# easda-schema.net
KiCad netlist of a schematic drawn in EasyEDA
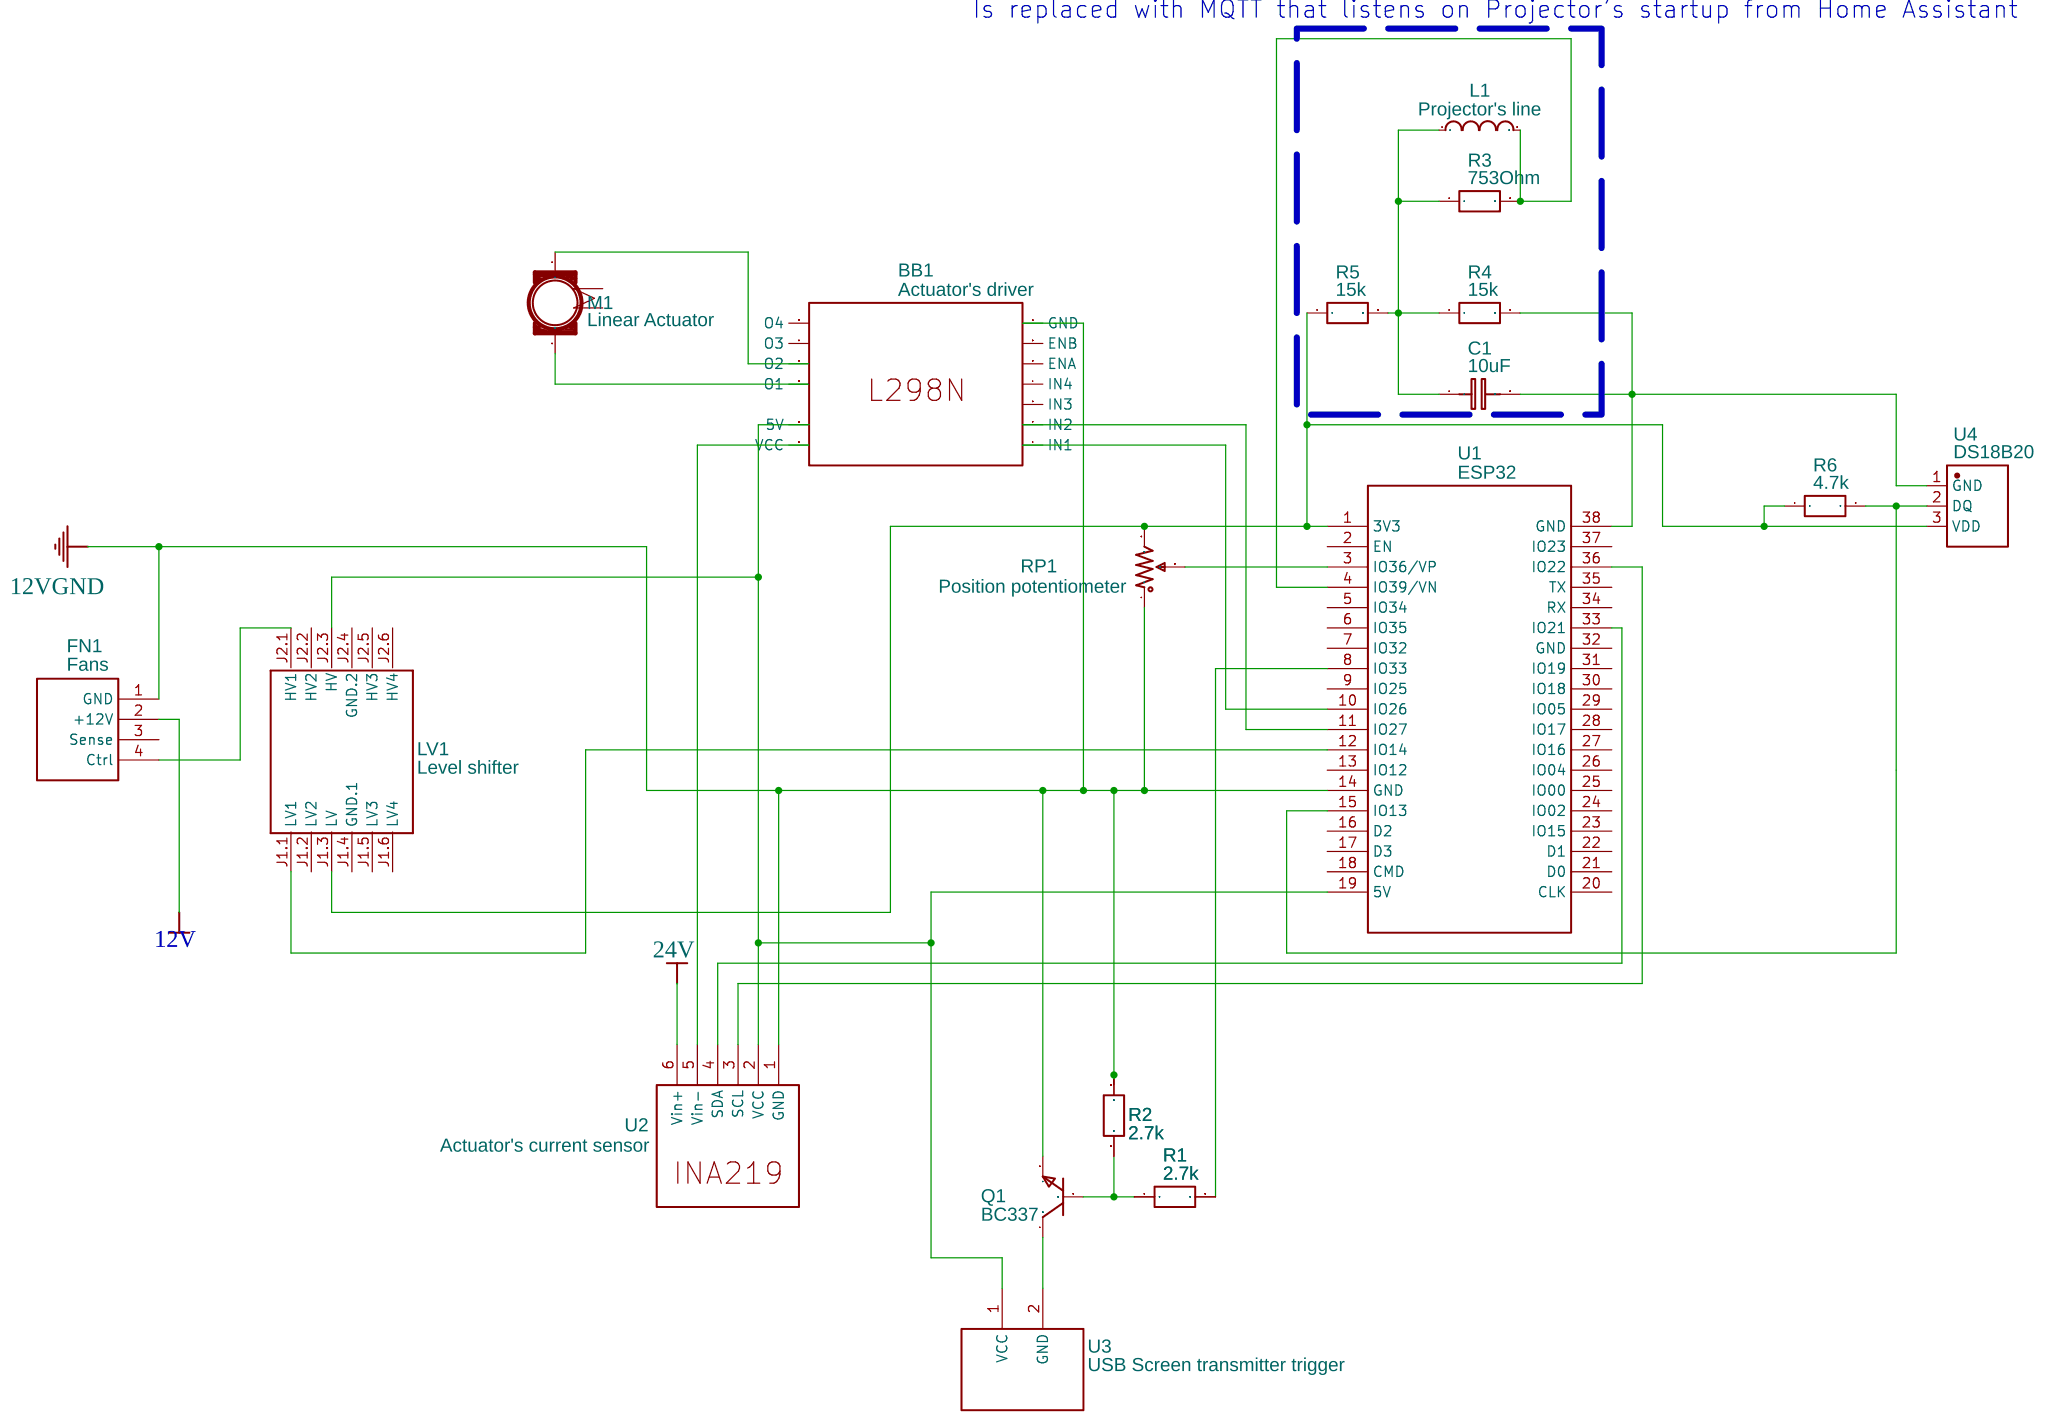
[diagram p0: schematic sheet]

(export (version "E")
  (design (tool "Eeschema 10.0.6"))
  (components
    (comp (ref "BB1") (value "Actuator's driver") (libsource (lib "") (part "L298N Breakout Board")))
    (comp (ref "C1") (value "10uF") (libsource (lib "") (part "C_0603_EU")))
    (comp (ref "FN1") (value "Fans") (libsource (lib "") (part "4 Pin PWM Fan Header")))
    (comp (ref "L1") (value "Projector's line") (libsource (lib "") (part "L0603_US")))
    (comp (ref "LV1") (value "Level shifter") (libsource (lib "") (part "LEVEL-SHIFTER-4CH")))
    (comp (ref "M1") (value "Linear Actuator") (libsource (lib "") (part "Motor_DC")))
    (comp (ref "Q1")
      (value "BC337")
      (fields (field (name "BOM_Supplier Part") "C154963"))
      (libsource (lib "") (part "BC337"))
    )
    (comp (ref "R1") (value "2.7k") (libsource (lib "") (part "R_0603_EU_1")))
    (comp (ref "R2") (value "2.7k") (libsource (lib "") (part "R_0603_EU")))
    (comp (ref "R3") (value "753Ohm") (libsource (lib "") (part "R_0603_EU_1")))
    (comp (ref "R4") (value "15k") (libsource (lib "") (part "R_0603_EU_1")))
    (comp (ref "R5") (value "15k") (libsource (lib "") (part "R_0603_EU_1")))
    (comp (ref "R6") (value "4.7k") (libsource (lib "") (part "R_0603_EU_1")))
    (comp (ref "RP1") (value "Position potentiometer") (libsource (lib "") (part "R_3386P_US")))
    (comp (ref "U1") (value "ESP32") (libsource (lib "") (part "ESP32-WROOM-32-D-U-DEVKIT-DOUBLE")))
    (comp (ref "U2") (value "Actuator's current sensor") (libsource (lib "") (part "INA219")))
    (comp (ref "U3")
      (value "USB Screen transmitter trigger")
      (libsource (lib "") (part "USB2-A-2P-FEMALE-SOCKET"))
    )
    (comp (ref "U4")
      (value "DS18B20")
      (fields (field (name "BOM_Supplier Part") "C376006"))
      (libsource (lib "") (part "DS18B20"))
    )
  )
  (nets
    (net (code "1") (name "12V") (class "Default")
      (node (ref "FN1") (pin "2") (pinfunction "+12V_2") (pintype "unspecified"))
    )
    (net (code "2") (name "12VGND") (class "Default")
      (node (ref "BB1") (pin "9") (pinfunction "GND_9") (pintype "unspecified"))
      (node (ref "FN1") (pin "1") (pinfunction "GND_1") (pintype "unspecified"))
      (node (ref "Q1") (pin "3") (pinfunction "E_3") (pintype "unspecified"))
      (node (ref "R2") (pin "2") (pinfunction "2_2") (pintype "unspecified"))
      (node (ref "RP1") (pin "1") (pinfunction "1_1") (pintype "unspecified"))
      (node (ref "U1") (pin "14") (pinfunction "GND_14") (pintype "unspecified"))
      (node (ref "U2") (pin "1") (pinfunction "GND_1") (pintype "unspecified"))
    )
    (net (code "3") (name "24V") (class "Default")
      (node (ref "U2") (pin "6") (pinfunction "Vin+_6") (pintype "unspecified"))
    )
    (net (code "4") (name "Net-(BB1-5V)") (class "Default")
      (node (ref "BB1") (pin "15") (pinfunction "5V_15") (pintype "unspecified"))
      (node (ref "LV1") (pin "J2.3") (pinfunction "HV_J2.3") (pintype "bidirectional"))
      (node (ref "U1") (pin "19") (pinfunction "5V_19") (pintype "unspecified"))
      (node (ref "U2") (pin "2") (pinfunction "VCC_2") (pintype "unspecified"))
      (node (ref "U3") (pin "1") (pinfunction "VCC_1") (pintype "unspecified"))
    )
    (net (code "5") (name "Net-(BB1-IN1)") (class "Default")
      (node (ref "BB1") (pin "1") (pinfunction "IN1_1") (pintype "unspecified"))
      (node (ref "U1") (pin "10") (pinfunction "IO26_10") (pintype "unspecified"))
    )
    (net (code "6") (name "Net-(BB1-IN2)") (class "Default")
      (node (ref "BB1") (pin "2") (pinfunction "IN2_2") (pintype "unspecified"))
      (node (ref "U1") (pin "11") (pinfunction "IO27_11") (pintype "unspecified"))
    )
    (net (code "7") (name "Net-(BB1-O1)") (class "Default")
      (node (ref "BB1") (pin "13") (pinfunction "O1_13") (pintype "unspecified"))
      (node (ref "M1") (pin "2") (pinfunction "2_2") (pintype "unspecified"))
    )
    (net (code "8") (name "Net-(BB1-O2)") (class "Default")
      (node (ref "BB1") (pin "12") (pinfunction "O2_12") (pintype "unspecified"))
      (node (ref "M1") (pin "1") (pinfunction "1_1") (pintype "unspecified"))
    )
    (net (code "9") (name "Net-(BB1-VCC)") (class "Default")
      (node (ref "BB1") (pin "14") (pinfunction "VCC_14") (pintype "unspecified"))
      (node (ref "U2") (pin "5") (pinfunction "Vin-_5") (pintype "unspecified"))
    )
    (net (code "10") (name "Net-(C1-Pad1)") (class "Default")
      (node (ref "C1") (pin "1") (pinfunction "1_1") (pintype "unspecified"))
      (node (ref "L1") (pin "1") (pinfunction "1_1") (pintype "unspecified"))
      (node (ref "R3") (pin "1") (pinfunction "1_1") (pintype "unspecified"))
      (node (ref "R4") (pin "1") (pinfunction "1_1") (pintype "unspecified"))
      (node (ref "R5") (pin "2") (pinfunction "2_2") (pintype "unspecified"))
    )
    (net (code "11") (name "Net-(FN1-Ctrl)") (class "Default")
      (node (ref "FN1") (pin "4") (pinfunction "Ctrl_4") (pintype "unspecified"))
      (node (ref "LV1") (pin "J2.1") (pinfunction "HV1_J2.1") (pintype "bidirectional"))
    )
    (net (code "12") (name "Net-(LV1-LV)") (class "Default")
      (node (ref "LV1") (pin "J1.3") (pinfunction "LV_J1.3") (pintype "bidirectional"))
      (node (ref "R5") (pin "1") (pinfunction "1_1") (pintype "unspecified"))
      (node (ref "R6") (pin "1") (pinfunction "1_1") (pintype "unspecified"))
      (node (ref "RP1") (pin "3") (pinfunction "3_3") (pintype "unspecified"))
      (node (ref "U1") (pin "1") (pinfunction "3V3_1") (pintype "unspecified"))
      (node (ref "U4") (pin "3") (pinfunction "VDD_3") (pintype "unspecified"))
    )
    (net (code "13") (name "Net-(LV1-LV1)") (class "Default")
      (node (ref "LV1") (pin "J1.1") (pinfunction "LV1_J1.1") (pintype "bidirectional"))
      (node (ref "U1") (pin "12") (pinfunction "IO14_12") (pintype "unspecified"))
    )
    (net (code "14") (name "Net-(Q1-B)") (class "Default")
      (node (ref "Q1") (pin "2") (pinfunction "B_2") (pintype "unspecified"))
      (node (ref "R1") (pin "1") (pinfunction "1_1") (pintype "unspecified"))
      (node (ref "R2") (pin "1") (pinfunction "1_1") (pintype "unspecified"))
    )
    (net (code "15") (name "Net-(Q1-C)") (class "Default")
      (node (ref "Q1") (pin "1") (pinfunction "C_1") (pintype "unspecified"))
      (node (ref "U3") (pin "2") (pinfunction "GND_2") (pintype "unspecified"))
    )
    (net (code "16") (name "Net-(U1-IO13)") (class "Default")
      (node (ref "R6") (pin "2") (pinfunction "2_2") (pintype "unspecified"))
      (node (ref "U1") (pin "15") (pinfunction "IO13_15") (pintype "unspecified"))
      (node (ref "U4") (pin "2") (pinfunction "DQ_2") (pintype "unspecified"))
    )
    (net (code "17") (name "Net-(U1-IO21)") (class "Default")
      (node (ref "U1") (pin "33") (pinfunction "IO21_33") (pintype "unspecified"))
      (node (ref "U2") (pin "4") (pinfunction "SDA_4") (pintype "unspecified"))
    )
    (net (code "18") (name "Net-(U1-IO22)") (class "Default")
      (node (ref "U1") (pin "36") (pinfunction "IO22_36") (pintype "unspecified"))
      (node (ref "U2") (pin "3") (pinfunction "SCL_3") (pintype "unspecified"))
    )
    (net (code "19") (name "Net-(U1-IO33)") (class "Default")
      (node (ref "R1") (pin "2") (pinfunction "2_2") (pintype "unspecified"))
      (node (ref "U1") (pin "8") (pinfunction "IO33_8") (pintype "unspecified"))
    )
    (net (code "20") (name "Net-(U1-IO36{slash}VP)") (class "Default")
      (node (ref "RP1") (pin "2") (pinfunction "2_2") (pintype "unspecified"))
      (node (ref "U1") (pin "3") (pinfunction "IO36/VP_3") (pintype "unspecified"))
    )
    (net (code "21") (name "Net-(U1-IO39{slash}VN)") (class "Default")
      (node (ref "L1") (pin "2") (pinfunction "2_2") (pintype "unspecified"))
      (node (ref "R3") (pin "2") (pinfunction "2_2") (pintype "unspecified"))
      (node (ref "U1") (pin "4") (pinfunction "IO39/VN_4") (pintype "unspecified"))
    )
    (net (code "22") (name "Net-(U4-GND)") (class "Default")
      (node (ref "C1") (pin "2") (pinfunction "2_2") (pintype "unspecified"))
      (node (ref "R4") (pin "2") (pinfunction "2_2") (pintype "unspecified"))
      (node (ref "U1") (pin "38") (pinfunction "GND_38") (pintype "unspecified"))
      (node (ref "U4") (pin "1") (pinfunction "GND_1") (pintype "unspecified"))
    )
    (net (code "23") (name "unconnected-(BB1-ENA-Pad5)") (class "Default")
      (node (ref "BB1") (pin "5") (pinfunction "ENA_5") (pintype "unspecified"))
    )
    (net (code "24") (name "unconnected-(BB1-ENB-Pad6)") (class "Default")
      (node (ref "BB1") (pin "6") (pinfunction "ENB_6") (pintype "unspecified"))
    )
    (net (code "25") (name "unconnected-(BB1-IN3-Pad3)") (class "Default")
      (node (ref "BB1") (pin "3") (pinfunction "IN3_3") (pintype "unspecified"))
    )
    (net (code "26") (name "unconnected-(BB1-IN4-Pad4)") (class "Default")
      (node (ref "BB1") (pin "4") (pinfunction "IN4_4") (pintype "unspecified"))
    )
    (net (code "27") (name "unconnected-(BB1-O3-Pad11)") (class "Default")
      (node (ref "BB1") (pin "11") (pinfunction "O3_11") (pintype "unspecified"))
    )
    (net (code "28") (name "unconnected-(BB1-O4-Pad10)") (class "Default")
      (node (ref "BB1") (pin "10") (pinfunction "O4_10") (pintype "unspecified"))
    )
    (net (code "29") (name "unconnected-(FN1-Sense-Pad3)") (class "Default")
      (node (ref "FN1") (pin "3") (pinfunction "Sense_3") (pintype "unspecified"))
    )
    (net (code "30") (name "unconnected-(LV1-GND.1-PadJ1.4)") (class "Default")
      (node (ref "LV1") (pin "J1.4") (pinfunction "GND.1_J1.4") (pintype "bidirectional"))
    )
    (net (code "31") (name "unconnected-(LV1-GND.2-PadJ2.4)") (class "Default")
      (node (ref "LV1") (pin "J2.4") (pinfunction "GND.2_J2.4") (pintype "bidirectional"))
    )
    (net (code "32") (name "unconnected-(LV1-HV2-PadJ2.2)") (class "Default")
      (node (ref "LV1") (pin "J2.2") (pinfunction "HV2_J2.2") (pintype "bidirectional"))
    )
    (net (code "33") (name "unconnected-(LV1-HV3-PadJ2.5)") (class "Default")
      (node (ref "LV1") (pin "J2.5") (pinfunction "HV3_J2.5") (pintype "bidirectional"))
    )
    (net (code "34") (name "unconnected-(LV1-HV4-PadJ2.6)") (class "Default")
      (node (ref "LV1") (pin "J2.6") (pinfunction "HV4_J2.6") (pintype "bidirectional"))
    )
    (net (code "35") (name "unconnected-(LV1-LV2-PadJ1.2)") (class "Default")
      (node (ref "LV1") (pin "J1.2") (pinfunction "LV2_J1.2") (pintype "bidirectional"))
    )
    (net (code "36") (name "unconnected-(LV1-LV3-PadJ1.5)") (class "Default")
      (node (ref "LV1") (pin "J1.5") (pinfunction "LV3_J1.5") (pintype "bidirectional"))
    )
    (net (code "37") (name "unconnected-(LV1-LV4-PadJ1.6)") (class "Default")
      (node (ref "LV1") (pin "J1.6") (pinfunction "LV4_J1.6") (pintype "bidirectional"))
    )
    (net (code "38") (name "unconnected-(U1-CLK-Pad20)") (class "Default")
      (node (ref "U1") (pin "20") (pinfunction "CLK_20") (pintype "unspecified"))
    )
    (net (code "39") (name "unconnected-(U1-CMD-Pad18)") (class "Default")
      (node (ref "U1") (pin "18") (pinfunction "CMD_18") (pintype "unspecified"))
    )
    (net (code "40") (name "unconnected-(U1-D0-Pad21)") (class "Default")
      (node (ref "U1") (pin "21") (pinfunction "D0_21") (pintype "unspecified"))
    )
    (net (code "41") (name "unconnected-(U1-D1-Pad22)") (class "Default")
      (node (ref "U1") (pin "22") (pinfunction "D1_22") (pintype "unspecified"))
    )
    (net (code "42") (name "unconnected-(U1-D2-Pad16)") (class "Default")
      (node (ref "U1") (pin "16") (pinfunction "D2_16") (pintype "unspecified"))
    )
    (net (code "43") (name "unconnected-(U1-D3-Pad17)") (class "Default")
      (node (ref "U1") (pin "17") (pinfunction "D3_17") (pintype "unspecified"))
    )
    (net (code "44") (name "unconnected-(U1-EN-Pad2)") (class "Default")
      (node (ref "U1") (pin "2") (pinfunction "EN_2") (pintype "unspecified"))
    )
    (net (code "45") (name "unconnected-(U1-GND-Pad32)") (class "Default")
      (node (ref "U1") (pin "32") (pinfunction "GND_32") (pintype "unspecified"))
    )
    (net (code "46") (name "unconnected-(U1-IO00-Pad25)") (class "Default")
      (node (ref "U1") (pin "25") (pinfunction "IO00_25") (pintype "unspecified"))
    )
    (net (code "47") (name "unconnected-(U1-IO02-Pad24)") (class "Default")
      (node (ref "U1") (pin "24") (pinfunction "IO02_24") (pintype "unspecified"))
    )
    (net (code "48") (name "unconnected-(U1-IO04-Pad26)") (class "Default")
      (node (ref "U1") (pin "26") (pinfunction "IO04_26") (pintype "unspecified"))
    )
    (net (code "49") (name "unconnected-(U1-IO05-Pad29)") (class "Default")
      (node (ref "U1") (pin "29") (pinfunction "IO05_29") (pintype "unspecified"))
    )
    (net (code "50") (name "unconnected-(U1-IO12-Pad13)") (class "Default")
      (node (ref "U1") (pin "13") (pinfunction "IO12_13") (pintype "unspecified"))
    )
    (net (code "51") (name "unconnected-(U1-IO15-Pad23)") (class "Default")
      (node (ref "U1") (pin "23") (pinfunction "IO15_23") (pintype "unspecified"))
    )
    (net (code "52") (name "unconnected-(U1-IO16-Pad27)") (class "Default")
      (node (ref "U1") (pin "27") (pinfunction "IO16_27") (pintype "unspecified"))
    )
    (net (code "53") (name "unconnected-(U1-IO17-Pad28)") (class "Default")
      (node (ref "U1") (pin "28") (pinfunction "IO17_28") (pintype "unspecified"))
    )
    (net (code "54") (name "unconnected-(U1-IO18-Pad30)") (class "Default")
      (node (ref "U1") (pin "30") (pinfunction "IO18_30") (pintype "unspecified"))
    )
    (net (code "55") (name "unconnected-(U1-IO19-Pad31)") (class "Default")
      (node (ref "U1") (pin "31") (pinfunction "IO19_31") (pintype "unspecified"))
    )
    (net (code "56") (name "unconnected-(U1-IO23-Pad37)") (class "Default")
      (node (ref "U1") (pin "37") (pinfunction "IO23_37") (pintype "unspecified"))
    )
    (net (code "57") (name "unconnected-(U1-IO25-Pad9)") (class "Default")
      (node (ref "U1") (pin "9") (pinfunction "IO25_9") (pintype "unspecified"))
    )
    (net (code "58") (name "unconnected-(U1-IO32-Pad7)") (class "Default")
      (node (ref "U1") (pin "7") (pinfunction "IO32_7") (pintype "unspecified"))
    )
    (net (code "59") (name "unconnected-(U1-IO34-Pad5)") (class "Default")
      (node (ref "U1") (pin "5") (pinfunction "IO34_5") (pintype "unspecified"))
    )
    (net (code "60") (name "unconnected-(U1-IO35-Pad6)") (class "Default")
      (node (ref "U1") (pin "6") (pinfunction "IO35_6") (pintype "unspecified"))
    )
    (net (code "61") (name "unconnected-(U1-RX-Pad34)") (class "Default")
      (node (ref "U1") (pin "34") (pinfunction "RX_34") (pintype "unspecified"))
    )
    (net (code "62") (name "unconnected-(U1-TX-Pad35)") (class "Default")
      (node (ref "U1") (pin "35") (pinfunction "TX_35") (pintype "unspecified"))
    )
  )
)
